# Pi_grammer_SPEEDY_SPI_V3.net
KiCad netlist of a schematic drawn in EAGLE
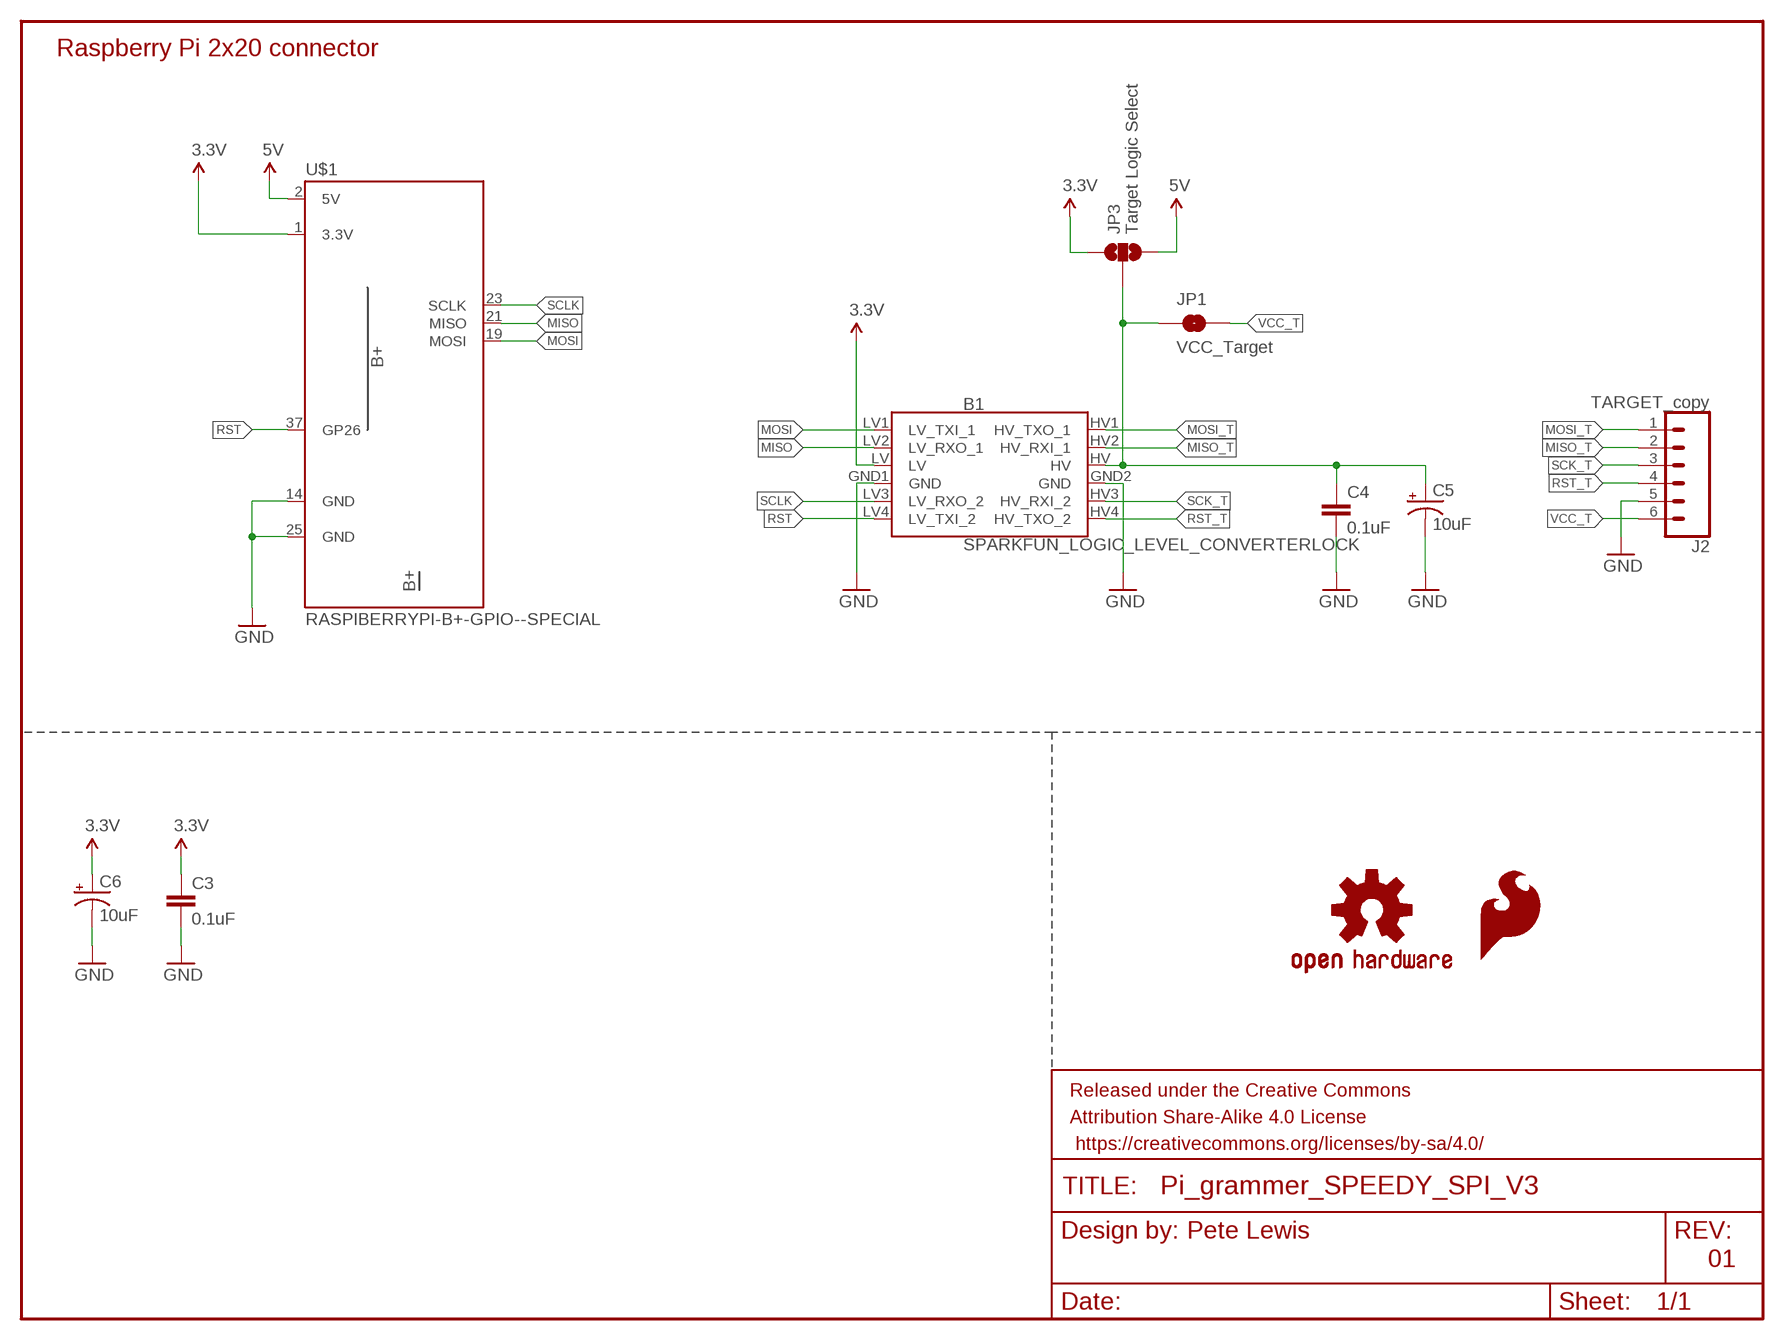
[diagram p0: schematic, sheet 1]

(export (version "E")
  (design (tool "Eeschema 10.0.6"))
  (components
    (comp (ref "B1")
      (value "SPARKFUN_LOGIC_LEVEL_CONVERTERLOCK")
      (footprint "eagle-import:SPARKFUN_LOGIC_LEVEL_CONVERTER_LOCK")
      (libsource (lib "eagle-import") (part "SPARKFUN_LOGIC_LEVEL_CONVERTERLOCK"))
    )
    (comp (ref "C3")
      (value "0.1uF")
      (footprint "eagle-import:0603")
      (libsource (lib "eagle-import") (part "0.1UF-0603-25V-(+80/-20%)"))
    )
    (comp (ref "C4")
      (value "0.1uF")
      (footprint "eagle-import:0603")
      (libsource (lib "eagle-import") (part "0.1UF-0603-25V-(+80/-20%)"))
    )
    (comp (ref "C5")
      (value "10uF")
      (footprint "eagle-import:EIA3216")
      (libsource (lib "eagle-import") (part "10UF-POLAR-EIA3216-16V-10%(TANT)"))
    )
    (comp (ref "C6")
      (value "10uF")
      (footprint "eagle-import:EIA3216")
      (libsource (lib "eagle-import") (part "10UF-POLAR-EIA3216-16V-10%(TANT)"))
    )
    (comp (ref "FRAME1")
      (value "FRAME-LETTER")
      (footprint "eagle-import:CREATIVE_COMMONS")
      (libsource (lib "eagle-import") (part "FRAME-LETTER"))
    )
    (comp (ref "J2")
      (value "TARGET_copy")
      (footprint "eagle-import:1X06-SIP_LOCK")
      (libsource (lib "eagle-import") (part "CONN_06SIP_LOCK"))
    )
    (comp (ref "JP1")
      (value "VCC_Target")
      (footprint "eagle-import:SMT-JUMPER_2_NO_SILK")
      (libsource (lib "eagle-import") (part "JUMPER-SMT_2_NO_SILK"))
    )
    (comp (ref "JP3")
      (value "Target Logic Select")
      (footprint "eagle-import:SMT-JUMPER_3_NO_SILK")
      (libsource (lib "eagle-import") (part "JUMPER-SMT_3_NO_SILK"))
    )
    (comp (ref "LOGO1")
      (value "SFE_LOGO_FLAME.1_INCH")
      (footprint "eagle-import:SFE_LOGO_FLAME_.1")
      (libsource (lib "eagle-import") (part "SFE_LOGO_FLAME.1_INCH"))
    )
    (comp (ref "LOGO2")
      (value "OSHW-LOGOS")
      (footprint "eagle-import:OSHW-LOGO-S")
      (libsource (lib "eagle-import") (part "OSHW-LOGOS"))
    )
    (comp (ref "U$1")
      (value "RASPIBERRYPI-B+-GPIO--SPECIAL")
      (footprint "eagle-import:2X20-SHROUDED--SPECIAL")
      (libsource (lib "eagle-import") (part "RASPIBERRYPI-B+-GPIO--SPECIAL"))
    )
  )
  (nets
    (net (code "1") (name "3.3V") (class "Default")
      (node (ref "B1") (pin "LV") (pinfunction "LV_LV") (pintype "power_in"))
      (node (ref "C3") (pin "1") (pinfunction "1_1") (pintype "passive"))
      (node (ref "C6") (pin "+") (pinfunction "+_+") (pintype "passive"))
      (node (ref "JP3") (pin "1") (pinfunction "1_1") (pintype "passive"))
      (node (ref "U$1") (pin "1") (pinfunction "3.3V_1") (pintype "power_in"))
    )
    (net (code "2") (name "5V") (class "Default")
      (node (ref "JP3") (pin "3") (pinfunction "3_3") (pintype "passive"))
      (node (ref "U$1") (pin "2") (pinfunction "5V_2") (pintype "power_in"))
    )
    (net (code "3") (name "GND") (class "Default")
      (node (ref "B1") (pin "GND1") (pinfunction "GND_GND1") (pintype "power_in"))
      (node (ref "B1") (pin "GND2") (pinfunction "GND_GND2") (pintype "power_in"))
      (node (ref "C3") (pin "2") (pinfunction "2_2") (pintype "passive"))
      (node (ref "C4") (pin "2") (pinfunction "2_2") (pintype "passive"))
      (node (ref "C5") (pin "-") (pinfunction "-_-") (pintype "passive"))
      (node (ref "C6") (pin "-") (pinfunction "-_-") (pintype "passive"))
      (node (ref "J2") (pin "5") (pinfunction "5_5") (pintype "passive"))
      (node (ref "U$1") (pin "14") (pinfunction "GND_14") (pintype "power_in"))
      (node (ref "U$1") (pin "25") (pinfunction "GND_25") (pintype "power_in"))
    )
    (net (code "4") (name "MISO") (class "Default")
      (node (ref "B1") (pin "LV2") (pinfunction "LV_RXO_1_LV2") (pintype "bidirectional"))
      (node (ref "U$1") (pin "21") (pinfunction "MISO_21") (pintype "input"))
    )
    (net (code "5") (name "MISO_T") (class "Default")
      (node (ref "B1") (pin "HV2") (pinfunction "HV_RXI_1_HV2") (pintype "bidirectional"))
      (node (ref "J2") (pin "2") (pinfunction "2_2") (pintype "passive"))
    )
    (net (code "6") (name "MOSI") (class "Default")
      (node (ref "B1") (pin "LV1") (pinfunction "LV_TXI_1_LV1") (pintype "bidirectional"))
      (node (ref "U$1") (pin "19") (pinfunction "MOSI_19") (pintype "output"))
    )
    (net (code "7") (name "MOSI_T") (class "Default")
      (node (ref "B1") (pin "HV1") (pinfunction "HV_TXO_1_HV1") (pintype "bidirectional"))
      (node (ref "J2") (pin "1") (pinfunction "1_1") (pintype "passive"))
    )
    (net (code "8") (name "Net-(B1-PadHV)") (class "Default")
      (node (ref "B1") (pin "HV") (pinfunction "HV_HV") (pintype "power_in"))
      (node (ref "C4") (pin "1") (pinfunction "1_1") (pintype "passive"))
      (node (ref "C5") (pin "+") (pinfunction "+_+") (pintype "passive"))
      (node (ref "JP1") (pin "1") (pinfunction "1_1") (pintype "passive"))
      (node (ref "JP3") (pin "2") (pinfunction "2_2") (pintype "passive"))
    )
    (net (code "9") (name "RST") (class "Default")
      (node (ref "B1") (pin "LV4") (pinfunction "LV_TXI_2_LV4") (pintype "bidirectional"))
      (node (ref "U$1") (pin "37") (pinfunction "GP26_37") (pintype "bidirectional"))
    )
    (net (code "10") (name "RST_T") (class "Default")
      (node (ref "B1") (pin "HV4") (pinfunction "HV_TXO_2_HV4") (pintype "bidirectional"))
      (node (ref "J2") (pin "4") (pinfunction "4_4") (pintype "passive"))
    )
    (net (code "11") (name "SCK_T") (class "Default")
      (node (ref "B1") (pin "HV3") (pinfunction "HV_RXI_2_HV3") (pintype "bidirectional"))
      (node (ref "J2") (pin "3") (pinfunction "3_3") (pintype "passive"))
    )
    (net (code "12") (name "SCLK") (class "Default")
      (node (ref "B1") (pin "LV3") (pinfunction "LV_RXO_2_LV3") (pintype "bidirectional"))
      (node (ref "U$1") (pin "23") (pinfunction "SCLK_23") (pintype "output"))
    )
    (net (code "13") (name "VCC_T") (class "Default")
      (node (ref "J2") (pin "6") (pinfunction "6_6") (pintype "passive"))
      (node (ref "JP1") (pin "2") (pinfunction "2_2") (pintype "passive"))
    )
  )
)
